# Sheet1.net
KiCad netlist of a schematic drawn in Altium Designer
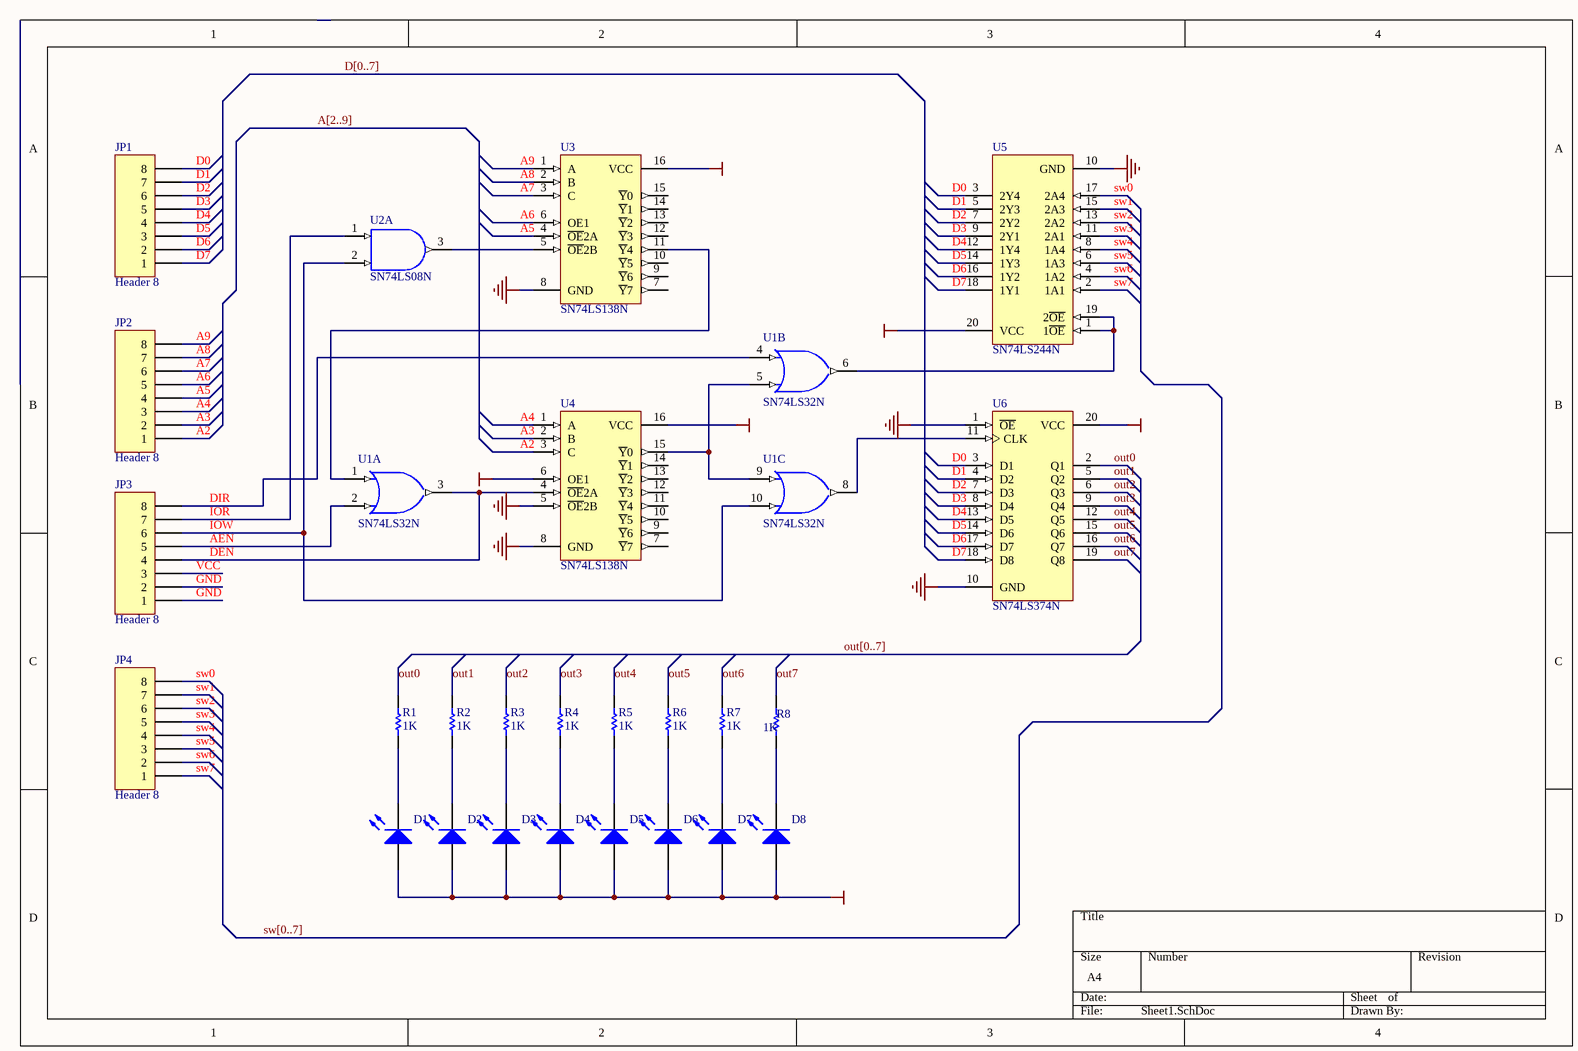
[diagram p0: Sheet1.SchDoc]

(export (version "E")
  (design (tool "Eeschema 10.0.6"))
  (components
    (comp (ref "D1")
      (value "LED1")
      (footprint "LED-1")
      (description "Typical RED GaAs LED")
      (fields (field (name "PUBLISHER") "Altium Limited"))
      (libsource (lib "Miscellaneous Devices") (part "LED1"))
    )
    (comp (ref "D2")
      (value "LED1")
      (footprint "LED-1")
      (description "Typical RED GaAs LED")
      (fields (field (name "PUBLISHER") "Altium Limited"))
      (libsource (lib "Miscellaneous Devices") (part "LED1"))
    )
    (comp (ref "D3")
      (value "LED1")
      (footprint "LED-1")
      (description "Typical RED GaAs LED")
      (fields (field (name "PUBLISHER") "Altium Limited"))
      (libsource (lib "Miscellaneous Devices") (part "LED1"))
    )
    (comp (ref "D4")
      (value "LED1")
      (footprint "LED-1")
      (description "Typical RED GaAs LED")
      (fields (field (name "PUBLISHER") "Altium Limited"))
      (libsource (lib "Miscellaneous Devices") (part "LED1"))
    )
    (comp (ref "D5")
      (value "LED1")
      (footprint "LED-1")
      (description "Typical RED GaAs LED")
      (fields (field (name "PUBLISHER") "Altium Limited"))
      (libsource (lib "Miscellaneous Devices") (part "LED1"))
    )
    (comp (ref "D6")
      (value "LED1")
      (footprint "LED-1")
      (description "Typical RED GaAs LED")
      (fields (field (name "PUBLISHER") "Altium Limited"))
      (libsource (lib "Miscellaneous Devices") (part "LED1"))
    )
    (comp (ref "D7")
      (value "LED1")
      (footprint "LED-1")
      (description "Typical RED GaAs LED")
      (fields (field (name "PUBLISHER") "Altium Limited"))
      (libsource (lib "Miscellaneous Devices") (part "LED1"))
    )
    (comp (ref "D8")
      (value "LED1")
      (footprint "LED-1")
      (description "Typical RED GaAs LED")
      (fields (field (name "PUBLISHER") "Altium Limited"))
      (libsource (lib "Miscellaneous Devices") (part "LED1"))
    )
    (comp (ref "JP1")
      (value "Header 8")
      (footprint "HDR1X8")
      (description "Header, 8-Pin")
      (fields (field (name "PUBLISHER") "Altium Limited"))
      (libsource (lib "Miscellaneous Connectors") (part "Header 8"))
    )
    (comp (ref "JP2")
      (value "Header 8")
      (footprint "HDR1X8")
      (description "Header, 8-Pin")
      (fields (field (name "PUBLISHER") "Altium Limited"))
      (libsource (lib "Miscellaneous Connectors") (part "Header 8"))
    )
    (comp (ref "JP3")
      (value "Header 8")
      (footprint "HDR1X8")
      (description "Header, 8-Pin")
      (fields (field (name "PUBLISHER") "Altium Limited"))
      (libsource (lib "Miscellaneous Connectors") (part "Header 8"))
    )
    (comp (ref "JP4")
      (value "Header 8")
      (footprint "HDR1X8")
      (description "Header, 8-Pin")
      (fields (field (name "PUBLISHER") "Altium Limited"))
      (libsource (lib "Miscellaneous Connectors") (part "Header 8"))
    )
    (comp (ref "R1")
      (value "1K")
      (footprint "AXIAL-0.3")
      (description "Resistor")
      (fields (field (name "Comment") "Res1") (field (name "PUBLISHER") "Altium Limited"))
      (libsource (lib "Miscellaneous Devices") (part "Res1"))
    )
    (comp (ref "R2")
      (value "1K")
      (footprint "AXIAL-0.3")
      (description "Resistor")
      (fields (field (name "Comment") "Res1") (field (name "PUBLISHER") "Altium Limited"))
      (libsource (lib "Miscellaneous Devices") (part "Res1"))
    )
    (comp (ref "R3")
      (value "1K")
      (footprint "AXIAL-0.3")
      (description "Resistor")
      (fields (field (name "Comment") "Res1") (field (name "PUBLISHER") "Altium Limited"))
      (libsource (lib "Miscellaneous Devices") (part "Res1"))
    )
    (comp (ref "R4")
      (value "1K")
      (footprint "AXIAL-0.3")
      (description "Resistor")
      (fields (field (name "Comment") "Res1") (field (name "PUBLISHER") "Altium Limited"))
      (libsource (lib "Miscellaneous Devices") (part "Res1"))
    )
    (comp (ref "R5")
      (value "1K")
      (footprint "AXIAL-0.3")
      (description "Resistor")
      (fields (field (name "Comment") "Res1") (field (name "PUBLISHER") "Altium Limited"))
      (libsource (lib "Miscellaneous Devices") (part "Res1"))
    )
    (comp (ref "R6")
      (value "1K")
      (footprint "AXIAL-0.3")
      (description "Resistor")
      (fields (field (name "Comment") "Res1") (field (name "PUBLISHER") "Altium Limited"))
      (libsource (lib "Miscellaneous Devices") (part "Res1"))
    )
    (comp (ref "R7")
      (value "1K")
      (footprint "AXIAL-0.3")
      (description "Resistor")
      (fields (field (name "Comment") "Res1") (field (name "PUBLISHER") "Altium Limited"))
      (libsource (lib "Miscellaneous Devices") (part "Res1"))
    )
    (comp (ref "R8")
      (value "1K")
      (footprint "AXIAL-0.3")
      (description "Resistor")
      (fields (field (name "Comment") "Res1") (field (name "PUBLISHER") "Altium Limited"))
      (libsource (lib "Miscellaneous Devices") (part "Res1"))
    )
    (comp (ref "U1")
      (value "SN74LS32N")
      (footprint "N014")
      (description "Quadruple 2-Input Positive-OR Gate")
      (fields (field (name "PUBLISHER") "Altium Limited"))
      (libsource (lib "TI Logic Gate 2") (part "SN74LS32N"))
    )
    (comp (ref "U2")
      (value "SN74LS08N")
      (footprint "N014")
      (description "Quadruple 2-Input Positive-AND Gate")
      (fields (field (name "PUBLISHER") "Altium Limited"))
      (libsource (lib "TI Logic Gate 2") (part "SN74LS08N"))
    )
    (comp (ref "U3")
      (value "SN74LS138N")
      (footprint "N016")
      (description "3-Line to 8-Line Decoder / Demultiplexer")
      (fields (field (name "PUBLISHER") "Altium Limited"))
      (libsource (lib "TI Logic Decoder Demux") (part "SN74LS138N"))
    )
    (comp (ref "U4")
      (value "SN74LS138N")
      (footprint "N016")
      (description "3-Line to 8-Line Decoder / Demultiplexer")
      (fields (field (name "PUBLISHER") "Altium Limited"))
      (libsource (lib "TI Logic Decoder Demux") (part "SN74LS138N"))
    )
    (comp (ref "U5")
      (value "SN74LS244N")
      (footprint "N020")
      (description "Octal Buffer and Line Driver with 3-State Outputs")
      (fields (field (name "PUBLISHER") "Altium Limited"))
      (libsource (lib "TI Logic Buffer Line Driver") (part "SN74LS244N"))
    )
    (comp (ref "U6")
      (value "SN74LS374N")
      (footprint "N020D")
      (description "Octal D-Type Transparent Latches and Edge-Triggered Flip-Flop")
      (fields (field (name "PUBLISHER") "Altium Limited"))
      (libsource (lib "TI Logic Flip-Flop") (part "SN74LS374N"))
    )
  )
  (nets
    (net (code "1") (name "/A2") (class "Default")
      (node (ref "JP2") (pin "1") (pinfunction "1_1") (pintype "passive"))
      (node (ref "U4") (pin "3") (pinfunction "C_3") (pintype "input"))
    )
    (net (code "2") (name "/A3") (class "Default")
      (node (ref "JP2") (pin "2") (pinfunction "2_2") (pintype "passive"))
      (node (ref "U4") (pin "2") (pinfunction "B_2") (pintype "input"))
    )
    (net (code "3") (name "/A4") (class "Default")
      (node (ref "JP2") (pin "3") (pinfunction "3_3") (pintype "passive"))
      (node (ref "U4") (pin "1") (pinfunction "A_1") (pintype "input"))
    )
    (net (code "4") (name "/A5") (class "Default")
      (node (ref "JP2") (pin "4") (pinfunction "4_4") (pintype "passive"))
      (node (ref "U3") (pin "4") (pinfunction "~{OE}2A_4") (pintype "input"))
    )
    (net (code "5") (name "/A6") (class "Default")
      (node (ref "JP2") (pin "5") (pinfunction "5_5") (pintype "passive"))
      (node (ref "U3") (pin "6") (pinfunction "OE1_6") (pintype "input"))
    )
    (net (code "6") (name "/A7") (class "Default")
      (node (ref "JP2") (pin "6") (pinfunction "6_6") (pintype "passive"))
      (node (ref "U3") (pin "3") (pinfunction "C_3") (pintype "input"))
    )
    (net (code "7") (name "/A8") (class "Default")
      (node (ref "JP2") (pin "7") (pinfunction "7_7") (pintype "passive"))
      (node (ref "U3") (pin "2") (pinfunction "B_2") (pintype "input"))
    )
    (net (code "8") (name "/A9") (class "Default")
      (node (ref "JP2") (pin "8") (pinfunction "8_8") (pintype "passive"))
      (node (ref "U3") (pin "1") (pinfunction "A_1") (pintype "input"))
    )
    (net (code "9") (name "/AEN") (class "Default")
      (node (ref "JP3") (pin "5") (pinfunction "5_5") (pintype "passive"))
      (node (ref "U1") (pin "2") (pinfunction "B_2") (pintype "input"))
    )
    (net (code "11") (name "/D0") (class "Default")
      (node (ref "JP1") (pin "8") (pinfunction "8_8") (pintype "passive"))
      (node (ref "U5") (pin "3") (pinfunction "2Y4_3") (pintype "tri_state"))
      (node (ref "U6") (pin "3") (pinfunction "D1_3") (pintype "input"))
    )
    (net (code "12") (name "/D1") (class "Default")
      (node (ref "JP1") (pin "7") (pinfunction "7_7") (pintype "passive"))
      (node (ref "U5") (pin "5") (pinfunction "2Y3_5") (pintype "tri_state"))
      (node (ref "U6") (pin "4") (pinfunction "D2_4") (pintype "input"))
    )
    (net (code "13") (name "/D2") (class "Default")
      (node (ref "JP1") (pin "6") (pinfunction "6_6") (pintype "passive"))
      (node (ref "U5") (pin "7") (pinfunction "2Y2_7") (pintype "tri_state"))
      (node (ref "U6") (pin "7") (pinfunction "D3_7") (pintype "input"))
    )
    (net (code "14") (name "/D3") (class "Default")
      (node (ref "JP1") (pin "5") (pinfunction "5_5") (pintype "passive"))
      (node (ref "U5") (pin "9") (pinfunction "2Y1_9") (pintype "tri_state"))
      (node (ref "U6") (pin "8") (pinfunction "D4_8") (pintype "input"))
    )
    (net (code "15") (name "/D4") (class "Default")
      (node (ref "JP1") (pin "4") (pinfunction "4_4") (pintype "passive"))
      (node (ref "U5") (pin "12") (pinfunction "1Y4_12") (pintype "tri_state"))
      (node (ref "U6") (pin "13") (pinfunction "D5_13") (pintype "input"))
    )
    (net (code "16") (name "/D5") (class "Default")
      (node (ref "JP1") (pin "3") (pinfunction "3_3") (pintype "passive"))
      (node (ref "U5") (pin "14") (pinfunction "1Y3_14") (pintype "tri_state"))
      (node (ref "U6") (pin "14") (pinfunction "D6_14") (pintype "input"))
    )
    (net (code "17") (name "/D6") (class "Default")
      (node (ref "JP1") (pin "2") (pinfunction "2_2") (pintype "passive"))
      (node (ref "U5") (pin "16") (pinfunction "1Y2_16") (pintype "tri_state"))
      (node (ref "U6") (pin "17") (pinfunction "D7_17") (pintype "input"))
    )
    (net (code "18") (name "/D7") (class "Default")
      (node (ref "JP1") (pin "1") (pinfunction "1_1") (pintype "passive"))
      (node (ref "U5") (pin "18") (pinfunction "1Y1_18") (pintype "tri_state"))
      (node (ref "U6") (pin "18") (pinfunction "D8_18") (pintype "input"))
    )
    (net (code "19") (name "/DEN") (class "Default")
      (node (ref "JP3") (pin "4") (pinfunction "4_4") (pintype "passive"))
      (node (ref "U1") (pin "3") (pinfunction "Y_3") (pintype "output"))
      (node (ref "U4") (pin "4") (pinfunction "~{OE}2A_4") (pintype "input"))
    )
    (net (code "20") (name "/DIR") (class "Default")
      (node (ref "JP3") (pin "8") (pinfunction "8_8") (pintype "passive"))
      (node (ref "U1") (pin "4") (pinfunction "A_4") (pintype "input"))
    )
    (net (code "22") (name "/IOR") (class "Default")
      (node (ref "JP3") (pin "7") (pinfunction "7_7") (pintype "passive"))
      (node (ref "U2") (pin "1") (pinfunction "A_1") (pintype "input"))
    )
    (net (code "23") (name "/IOW") (class "Default")
      (node (ref "JP3") (pin "6") (pinfunction "6_6") (pintype "passive"))
      (node (ref "U1") (pin "10") (pinfunction "B_10") (pintype "input"))
      (node (ref "U2") (pin "2") (pinfunction "B_2") (pintype "input"))
    )
    (net (code "24") (name "/out0") (class "Default")
      (node (ref "R1") (pin "1") (pinfunction "1_1") (pintype "passive"))
      (node (ref "U6") (pin "2") (pinfunction "Q1_2") (pintype "tri_state"))
    )
    (net (code "25") (name "/out1") (class "Default")
      (node (ref "R2") (pin "2") (pinfunction "2_2") (pintype "passive"))
      (node (ref "U6") (pin "5") (pinfunction "Q2_5") (pintype "tri_state"))
    )
    (net (code "26") (name "/out2") (class "Default")
      (node (ref "R3") (pin "2") (pinfunction "2_2") (pintype "passive"))
      (node (ref "U6") (pin "6") (pinfunction "Q3_6") (pintype "tri_state"))
    )
    (net (code "27") (name "/out3") (class "Default")
      (node (ref "R4") (pin "2") (pinfunction "2_2") (pintype "passive"))
      (node (ref "U6") (pin "9") (pinfunction "Q4_9") (pintype "tri_state"))
    )
    (net (code "28") (name "/out4") (class "Default")
      (node (ref "R5") (pin "2") (pinfunction "2_2") (pintype "passive"))
      (node (ref "U6") (pin "12") (pinfunction "Q5_12") (pintype "tri_state"))
    )
    (net (code "29") (name "/out5") (class "Default")
      (node (ref "R6") (pin "2") (pinfunction "2_2") (pintype "passive"))
      (node (ref "U6") (pin "15") (pinfunction "Q6_15") (pintype "tri_state"))
    )
    (net (code "30") (name "/out6") (class "Default")
      (node (ref "R7") (pin "2") (pinfunction "2_2") (pintype "passive"))
      (node (ref "U6") (pin "16") (pinfunction "Q7_16") (pintype "tri_state"))
    )
    (net (code "31") (name "/out7") (class "Default")
      (node (ref "R8") (pin "2") (pinfunction "2_2") (pintype "passive"))
      (node (ref "U6") (pin "19") (pinfunction "Q8_19") (pintype "tri_state"))
    )
    (net (code "33") (name "/sw0") (class "Default")
      (node (ref "JP4") (pin "8") (pinfunction "8_8") (pintype "passive"))
      (node (ref "U5") (pin "17") (pinfunction "2A4_17") (pintype "input"))
    )
    (net (code "34") (name "/sw1") (class "Default")
      (node (ref "JP4") (pin "7") (pinfunction "7_7") (pintype "passive"))
      (node (ref "U5") (pin "15") (pinfunction "2A3_15") (pintype "input"))
    )
    (net (code "35") (name "/sw2") (class "Default")
      (node (ref "JP4") (pin "6") (pinfunction "6_6") (pintype "passive"))
      (node (ref "U5") (pin "13") (pinfunction "2A2_13") (pintype "input"))
    )
    (net (code "36") (name "/sw3") (class "Default")
      (node (ref "JP4") (pin "5") (pinfunction "5_5") (pintype "passive"))
      (node (ref "U5") (pin "11") (pinfunction "2A1_11") (pintype "input"))
    )
    (net (code "37") (name "/sw4") (class "Default")
      (node (ref "JP4") (pin "4") (pinfunction "4_4") (pintype "passive"))
      (node (ref "U5") (pin "8") (pinfunction "1A4_8") (pintype "input"))
    )
    (net (code "38") (name "/sw5") (class "Default")
      (node (ref "JP4") (pin "3") (pinfunction "3_3") (pintype "passive"))
      (node (ref "U5") (pin "6") (pinfunction "1A3_6") (pintype "input"))
    )
    (net (code "39") (name "/sw6") (class "Default")
      (node (ref "JP4") (pin "2") (pinfunction "2_2") (pintype "passive"))
      (node (ref "U5") (pin "4") (pinfunction "1A2_4") (pintype "input"))
    )
    (net (code "40") (name "/sw7") (class "Default")
      (node (ref "JP4") (pin "1") (pinfunction "1_1") (pintype "passive"))
      (node (ref "U5") (pin "2") (pinfunction "1A1_2") (pintype "input"))
    )
    (net (code "42") (name "GND") (class "Default")
      (node (ref "JP3") (pin "1") (pinfunction "1_1") (pintype "passive"))
      (node (ref "JP3") (pin "2") (pinfunction "2_2") (pintype "passive"))
      (node (ref "U1") (pin "7") (pinfunction "GND_7") (pintype "power_in"))
      (node (ref "U2") (pin "7") (pinfunction "GND_7") (pintype "power_in"))
      (node (ref "U3") (pin "8") (pinfunction "GND_8") (pintype "power_in"))
      (node (ref "U4") (pin "5") (pinfunction "~{OE}2B_5") (pintype "input"))
      (node (ref "U4") (pin "8") (pinfunction "GND_8") (pintype "power_in"))
      (node (ref "U5") (pin "10") (pinfunction "GND_10") (pintype "power_in"))
      (node (ref "U6") (pin "1") (pinfunction "~{OE}_1") (pintype "input"))
      (node (ref "U6") (pin "10") (pinfunction "GND_10") (pintype "power_in"))
    )
    (net (code "43") (name "Net-(D1-K)") (class "Default")
      (node (ref "D1") (pin "2") (pinfunction "K_2") (pintype "passive"))
      (node (ref "R1") (pin "2") (pinfunction "2_2") (pintype "passive"))
    )
    (net (code "44") (name "Net-(D2-K)") (class "Default")
      (node (ref "D2") (pin "2") (pinfunction "K_2") (pintype "passive"))
      (node (ref "R2") (pin "1") (pinfunction "1_1") (pintype "passive"))
    )
    (net (code "45") (name "Net-(D3-K)") (class "Default")
      (node (ref "D3") (pin "2") (pinfunction "K_2") (pintype "passive"))
      (node (ref "R3") (pin "1") (pinfunction "1_1") (pintype "passive"))
    )
    (net (code "46") (name "Net-(D4-K)") (class "Default")
      (node (ref "D4") (pin "2") (pinfunction "K_2") (pintype "passive"))
      (node (ref "R4") (pin "1") (pinfunction "1_1") (pintype "passive"))
    )
    (net (code "47") (name "Net-(D5-K)") (class "Default")
      (node (ref "D5") (pin "2") (pinfunction "K_2") (pintype "passive"))
      (node (ref "R5") (pin "1") (pinfunction "1_1") (pintype "passive"))
    )
    (net (code "48") (name "Net-(D6-K)") (class "Default")
      (node (ref "D6") (pin "2") (pinfunction "K_2") (pintype "passive"))
      (node (ref "R6") (pin "1") (pinfunction "1_1") (pintype "passive"))
    )
    (net (code "49") (name "Net-(D7-K)") (class "Default")
      (node (ref "D7") (pin "2") (pinfunction "K_2") (pintype "passive"))
      (node (ref "R7") (pin "1") (pinfunction "1_1") (pintype "passive"))
    )
    (net (code "50") (name "Net-(D8-K)") (class "Default")
      (node (ref "D8") (pin "2") (pinfunction "K_2") (pintype "passive"))
      (node (ref "R8") (pin "1") (pinfunction "1_1") (pintype "passive"))
    )
    (net (code "51") (name "Net-(U1A-A)") (class "Default")
      (node (ref "U1") (pin "1") (pinfunction "A_1") (pintype "input"))
      (node (ref "U3") (pin "11") (pinfunction "~{Y}4_11") (pintype "output"))
    )
    (net (code "52") (name "Net-(U1B-B)") (class "Default")
      (node (ref "U1") (pin "5") (pinfunction "B_5") (pintype "input"))
      (node (ref "U1") (pin "9") (pinfunction "A_9") (pintype "input"))
      (node (ref "U4") (pin "15") (pinfunction "~{Y}0_15") (pintype "output"))
    )
    (net (code "53") (name "Net-(U1B-Y)") (class "Default")
      (node (ref "U1") (pin "6") (pinfunction "Y_6") (pintype "output"))
      (node (ref "U5") (pin "1") (pinfunction "1~{OE}_1") (pintype "input"))
      (node (ref "U5") (pin "19") (pinfunction "2~{OE}_19") (pintype "input"))
    )
    (net (code "54") (name "Net-(U1C-Y)") (class "Default")
      (node (ref "U1") (pin "8") (pinfunction "Y_8") (pintype "output"))
      (node (ref "U6") (pin "11") (pinfunction "CLK_11") (pintype "input"))
    )
    (net (code "55") (name "Net-(U2A-Y)") (class "Default")
      (node (ref "U2") (pin "3") (pinfunction "Y_3") (pintype "output"))
      (node (ref "U3") (pin "5") (pinfunction "~{OE}2B_5") (pintype "input"))
    )
    (net (code "56") (name "VCC") (class "Default")
      (node (ref "D1") (pin "1") (pinfunction "A_1") (pintype "passive"))
      (node (ref "D2") (pin "1") (pinfunction "A_1") (pintype "passive"))
      (node (ref "D3") (pin "1") (pinfunction "A_1") (pintype "passive"))
      (node (ref "D4") (pin "1") (pinfunction "A_1") (pintype "passive"))
      (node (ref "D5") (pin "1") (pinfunction "A_1") (pintype "passive"))
      (node (ref "D6") (pin "1") (pinfunction "A_1") (pintype "passive"))
      (node (ref "D7") (pin "1") (pinfunction "A_1") (pintype "passive"))
      (node (ref "D8") (pin "1") (pinfunction "A_1") (pintype "passive"))
      (node (ref "JP3") (pin "3") (pinfunction "3_3") (pintype "passive"))
      (node (ref "U1") (pin "14") (pinfunction "VCC_14") (pintype "power_in"))
      (node (ref "U2") (pin "14") (pinfunction "VCC_14") (pintype "power_in"))
      (node (ref "U3") (pin "16") (pinfunction "VCC_16") (pintype "power_in"))
      (node (ref "U4") (pin "16") (pinfunction "VCC_16") (pintype "power_in"))
      (node (ref "U4") (pin "6") (pinfunction "OE1_6") (pintype "input"))
      (node (ref "U5") (pin "20") (pinfunction "VCC_20") (pintype "power_in"))
      (node (ref "U6") (pin "20") (pinfunction "VCC_20") (pintype "power_in"))
    )
    (net (code "57") (name "unconnected-(U3-~{Y}0-Pad15)") (class "Default")
      (node (ref "U3") (pin "15") (pinfunction "~{Y}0_15") (pintype "output"))
    )
    (net (code "58") (name "unconnected-(U3-~{Y}1-Pad14)") (class "Default")
      (node (ref "U3") (pin "14") (pinfunction "~{Y}1_14") (pintype "output"))
    )
    (net (code "59") (name "unconnected-(U3-~{Y}2-Pad13)") (class "Default")
      (node (ref "U3") (pin "13") (pinfunction "~{Y}2_13") (pintype "output"))
    )
    (net (code "60") (name "unconnected-(U3-~{Y}3-Pad12)") (class "Default")
      (node (ref "U3") (pin "12") (pinfunction "~{Y}3_12") (pintype "output"))
    )
    (net (code "61") (name "unconnected-(U3-~{Y}5-Pad10)") (class "Default")
      (node (ref "U3") (pin "10") (pinfunction "~{Y}5_10") (pintype "output"))
    )
    (net (code "62") (name "unconnected-(U3-~{Y}6-Pad9)") (class "Default")
      (node (ref "U3") (pin "9") (pinfunction "~{Y}6_9") (pintype "output"))
    )
    (net (code "63") (name "unconnected-(U3-~{Y}7-Pad7)") (class "Default")
      (node (ref "U3") (pin "7") (pinfunction "~{Y}7_7") (pintype "output"))
    )
    (net (code "64") (name "unconnected-(U4-~{Y}1-Pad14)") (class "Default")
      (node (ref "U4") (pin "14") (pinfunction "~{Y}1_14") (pintype "output"))
    )
    (net (code "65") (name "unconnected-(U4-~{Y}2-Pad13)") (class "Default")
      (node (ref "U4") (pin "13") (pinfunction "~{Y}2_13") (pintype "output"))
    )
    (net (code "66") (name "unconnected-(U4-~{Y}3-Pad12)") (class "Default")
      (node (ref "U4") (pin "12") (pinfunction "~{Y}3_12") (pintype "output"))
    )
    (net (code "67") (name "unconnected-(U4-~{Y}4-Pad11)") (class "Default")
      (node (ref "U4") (pin "11") (pinfunction "~{Y}4_11") (pintype "output"))
    )
    (net (code "68") (name "unconnected-(U4-~{Y}5-Pad10)") (class "Default")
      (node (ref "U4") (pin "10") (pinfunction "~{Y}5_10") (pintype "output"))
    )
    (net (code "69") (name "unconnected-(U4-~{Y}6-Pad9)") (class "Default")
      (node (ref "U4") (pin "9") (pinfunction "~{Y}6_9") (pintype "output"))
    )
    (net (code "70") (name "unconnected-(U4-~{Y}7-Pad7)") (class "Default")
      (node (ref "U4") (pin "7") (pinfunction "~{Y}7_7") (pintype "output"))
    )
  )
)
